# Volumetric_Control_Board.net
KiCad netlist of a schematic drawn in EAGLE
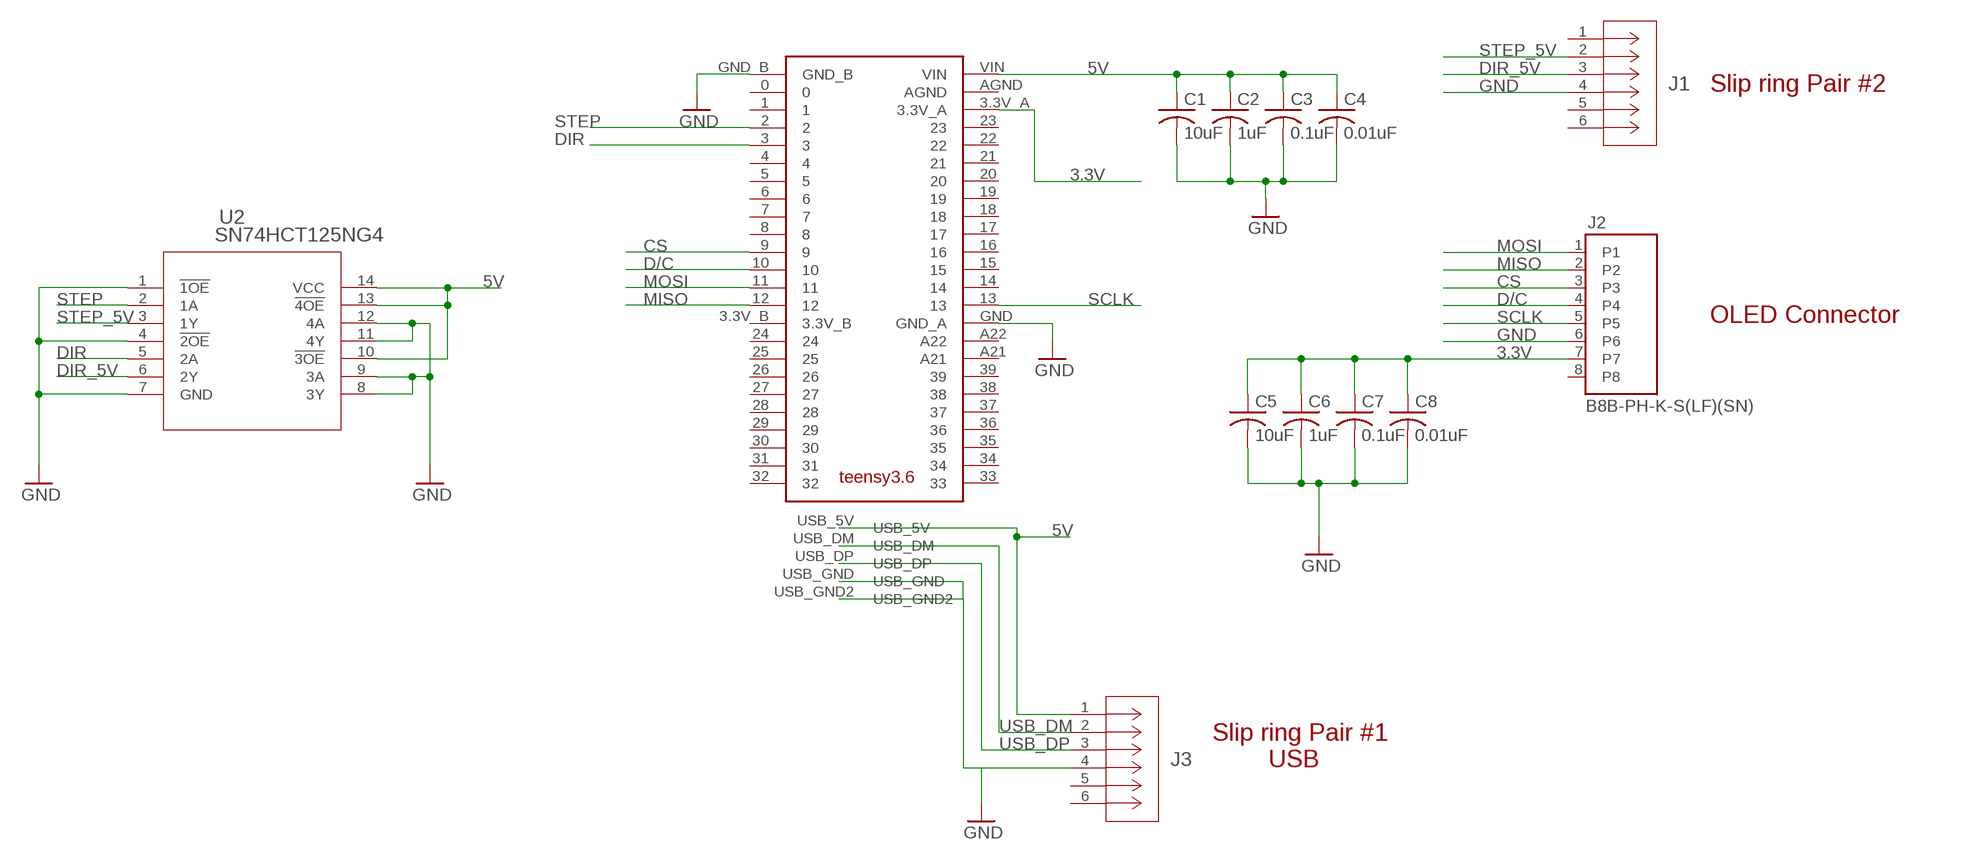
[diagram p0: schematic, sheet 1]

(export (version "E")
  (design (tool "Eeschema 10.0.6"))
  (components
    (comp (ref "C1")
      (value "10uF")
      (footprint "eagle-import:C1206")
      (libsource (lib "eagle-import") (part "C-USC1206"))
    )
    (comp (ref "C2")
      (value "1uF")
      (footprint "eagle-import:C1206")
      (libsource (lib "eagle-import") (part "C-USC1206"))
    )
    (comp (ref "C3")
      (value "0.1uF")
      (footprint "eagle-import:C1206")
      (libsource (lib "eagle-import") (part "C-USC1206"))
    )
    (comp (ref "C4")
      (value "0.01uF")
      (footprint "eagle-import:C1206")
      (libsource (lib "eagle-import") (part "C-USC1206"))
    )
    (comp (ref "C5")
      (value "10uF")
      (footprint "eagle-import:C1206")
      (libsource (lib "eagle-import") (part "C-USC1206"))
    )
    (comp (ref "C6")
      (value "1uF")
      (footprint "eagle-import:C1206")
      (libsource (lib "eagle-import") (part "C-USC1206"))
    )
    (comp (ref "C7")
      (value "0.1uF")
      (footprint "eagle-import:C1206")
      (libsource (lib "eagle-import") (part "C-USC1206"))
    )
    (comp (ref "C8")
      (value "0.01uF")
      (footprint "eagle-import:C1206")
      (libsource (lib "eagle-import") (part "C-USC1206"))
    )
    (comp (ref "J1")
      (value "B6B-PH-K-S(LF)(SN)")
      (footprint "eagle-import:CONN_B6B-PH-K-S_JST")
      (fields (field (name "COPYRIGHT") "Copyright (C) 2021 Ultra Librarian. All rights reserved."))
      (libsource (lib "eagle-import") (part "B6B-PH-K-S(LF)(SN)"))
    )
    (comp (ref "J2")
      (value "B8B-PH-K-S(LF)(SN)")
      (footprint "eagle-import:JST_B8B-PH-K-S(LF)(SN)")
      (fields (field (name "DIGI-KEY_PART_NUMBER") "455-1710-ND") (field (name "MF") "JST Sales"))
      (libsource (lib "eagle-import") (part "B8B-PH-K-S(LF)(SN)"))
    )
    (comp (ref "J3")
      (value "B6B-PH-K-S(LF)(SN)")
      (footprint "eagle-import:CONN_B6B-PH-K-S_JST")
      (fields (field (name "COPYRIGHT") "Copyright (C) 2021 Ultra Librarian. All rights reserved."))
      (libsource (lib "eagle-import") (part "B6B-PH-K-S(LF)(SN)"))
    )
    (comp (ref "U$1")
      (value "TEENSY3.6")
      (footprint "eagle-import:TEENSY3.6")
      (libsource (lib "eagle-import") (part "TEENSY3.6"))
    )
    (comp (ref "U2")
      (value "SN74HCT125NG4")
      (footprint "eagle-import:N14_TEX")
      (fields (field (name "COPYRIGHT") "Copyright (C) 2021 Ultra Librarian. All rights reserved."))
      (libsource (lib "eagle-import") (part "SN74HCT125NG4"))
    )
  )
  (nets
    (net (code "1") (name "/3.3V") (class "Default")
      (node (ref "C5") (pin "1") (pinfunction "1_1") (pintype "passive"))
      (node (ref "C6") (pin "1") (pinfunction "1_1") (pintype "passive"))
      (node (ref "C7") (pin "1") (pinfunction "1_1") (pintype "passive"))
      (node (ref "C8") (pin "1") (pinfunction "1_1") (pintype "passive"))
      (node (ref "J2") (pin "7") (pinfunction "P7_7") (pintype "passive"))
      (node (ref "U$1") (pin "3.3V_A") (pinfunction "3.3V_A_3.3V_A") (pintype "bidirectional"))
    )
    (net (code "2") (name "/5V") (class "Default")
      (node (ref "C1") (pin "1") (pinfunction "1_1") (pintype "passive"))
      (node (ref "C2") (pin "1") (pinfunction "1_1") (pintype "passive"))
      (node (ref "C3") (pin "1") (pinfunction "1_1") (pintype "passive"))
      (node (ref "C4") (pin "1") (pinfunction "1_1") (pintype "passive"))
      (node (ref "J3") (pin "1") (pinfunction "1_1") (pintype "passive"))
      (node (ref "U$1") (pin "USB_5V") (pinfunction "USB_5V_USB_5V") (pintype "bidirectional"))
      (node (ref "U$1") (pin "VIN") (pinfunction "VIN_VIN") (pintype "bidirectional"))
      (node (ref "U2") (pin "10") (pinfunction "~{3OE}_10") (pintype "input"))
      (node (ref "U2") (pin "13") (pinfunction "~{4OE}_13") (pintype "input"))
      (node (ref "U2") (pin "14") (pinfunction "VCC_14") (pintype "passive"))
    )
    (net (code "3") (name "/CS") (class "Default")
      (node (ref "J2") (pin "3") (pinfunction "P3_3") (pintype "passive"))
      (node (ref "U$1") (pin "9") (pinfunction "9_9") (pintype "bidirectional"))
    )
    (net (code "4") (name "/DIR") (class "Default")
      (node (ref "U$1") (pin "3") (pinfunction "3_3") (pintype "bidirectional"))
      (node (ref "U2") (pin "5") (pinfunction "2A_5") (pintype "input"))
    )
    (net (code "5") (name "/DIR_5V") (class "Default")
      (node (ref "J1") (pin "3") (pinfunction "3_3") (pintype "passive"))
      (node (ref "U2") (pin "6") (pinfunction "2Y_6") (pintype "tri_state"))
    )
    (net (code "6") (name "/D{slash}C") (class "Default")
      (node (ref "J2") (pin "4") (pinfunction "P4_4") (pintype "passive"))
      (node (ref "U$1") (pin "10") (pinfunction "10_10") (pintype "bidirectional"))
    )
    (net (code "7") (name "/MISO") (class "Default")
      (node (ref "J2") (pin "2") (pinfunction "P2_2") (pintype "passive"))
      (node (ref "U$1") (pin "12") (pinfunction "12_12") (pintype "bidirectional"))
    )
    (net (code "8") (name "/MOSI") (class "Default")
      (node (ref "J2") (pin "1") (pinfunction "P1_1") (pintype "passive"))
      (node (ref "U$1") (pin "11") (pinfunction "11_11") (pintype "bidirectional"))
    )
    (net (code "9") (name "/SCLK") (class "Default")
      (node (ref "J2") (pin "5") (pinfunction "P5_5") (pintype "passive"))
      (node (ref "U$1") (pin "13") (pinfunction "13_13") (pintype "bidirectional"))
    )
    (net (code "10") (name "/STEP") (class "Default")
      (node (ref "U$1") (pin "2") (pinfunction "2_2") (pintype "bidirectional"))
      (node (ref "U2") (pin "2") (pinfunction "1A_2") (pintype "input"))
    )
    (net (code "11") (name "/STEP_5V") (class "Default")
      (node (ref "J1") (pin "2") (pinfunction "2_2") (pintype "passive"))
      (node (ref "U2") (pin "3") (pinfunction "1Y_3") (pintype "tri_state"))
    )
    (net (code "12") (name "/USB_DM") (class "Default")
      (node (ref "J3") (pin "2") (pinfunction "2_2") (pintype "passive"))
      (node (ref "U$1") (pin "USB_DM") (pinfunction "USB_DM_USB_DM") (pintype "bidirectional"))
    )
    (net (code "13") (name "/USB_DP") (class "Default")
      (node (ref "J3") (pin "3") (pinfunction "3_3") (pintype "passive"))
      (node (ref "U$1") (pin "USB_DP") (pinfunction "USB_DP_USB_DP") (pintype "bidirectional"))
    )
    (net (code "14") (name "GND") (class "Default")
      (node (ref "C1") (pin "2") (pinfunction "2_2") (pintype "passive"))
      (node (ref "C2") (pin "2") (pinfunction "2_2") (pintype "passive"))
      (node (ref "C3") (pin "2") (pinfunction "2_2") (pintype "passive"))
      (node (ref "C4") (pin "2") (pinfunction "2_2") (pintype "passive"))
      (node (ref "C5") (pin "2") (pinfunction "2_2") (pintype "passive"))
      (node (ref "C6") (pin "2") (pinfunction "2_2") (pintype "passive"))
      (node (ref "C7") (pin "2") (pinfunction "2_2") (pintype "passive"))
      (node (ref "C8") (pin "2") (pinfunction "2_2") (pintype "passive"))
      (node (ref "J1") (pin "4") (pinfunction "4_4") (pintype "passive"))
      (node (ref "J2") (pin "6") (pinfunction "P6_6") (pintype "passive"))
      (node (ref "J3") (pin "4") (pinfunction "4_4") (pintype "passive"))
      (node (ref "U$1") (pin "GND") (pinfunction "GND_A_GND") (pintype "bidirectional"))
      (node (ref "U$1") (pin "GND_B") (pinfunction "GND_B_GND_B") (pintype "bidirectional"))
      (node (ref "U$1") (pin "USB_GND") (pinfunction "USB_GND_USB_GND") (pintype "bidirectional"))
      (node (ref "U$1") (pin "USB_GND2") (pinfunction "USB_GND2_USB_GND2") (pintype "bidirectional"))
      (node (ref "U2") (pin "1") (pinfunction "~{1OE}_1") (pintype "input"))
      (node (ref "U2") (pin "11") (pinfunction "4Y_11") (pintype "tri_state"))
      (node (ref "U2") (pin "12") (pinfunction "4A_12") (pintype "input"))
      (node (ref "U2") (pin "4") (pinfunction "~{2OE}_4") (pintype "input"))
      (node (ref "U2") (pin "7") (pinfunction "GND_7") (pintype "passive"))
      (node (ref "U2") (pin "8") (pinfunction "3Y_8") (pintype "tri_state"))
      (node (ref "U2") (pin "9") (pinfunction "3A_9") (pintype "input"))
    )
    (net (code "15") (name "unconnected-(J1-Pad1)") (class "Default")
      (node (ref "J1") (pin "1") (pinfunction "1_1") (pintype "passive"))
    )
    (net (code "16") (name "unconnected-(J1-Pad5)") (class "Default")
      (node (ref "J1") (pin "5") (pinfunction "5_5") (pintype "passive"))
    )
    (net (code "17") (name "unconnected-(J1-Pad6)") (class "Default")
      (node (ref "J1") (pin "6") (pinfunction "6_6") (pintype "passive"))
    )
    (net (code "18") (name "unconnected-(J2-P8-Pad8)") (class "Default")
      (node (ref "J2") (pin "8") (pinfunction "P8_8") (pintype "passive"))
    )
    (net (code "19") (name "unconnected-(J3-Pad5)") (class "Default")
      (node (ref "J3") (pin "5") (pinfunction "5_5") (pintype "passive"))
    )
    (net (code "20") (name "unconnected-(J3-Pad6)") (class "Default")
      (node (ref "J3") (pin "6") (pinfunction "6_6") (pintype "passive"))
    )
    (net (code "21") (name "unconnected-(U$1-Pad0)") (class "Default")
      (node (ref "U$1") (pin "0") (pinfunction "0_0") (pintype "bidirectional"))
    )
    (net (code "22") (name "unconnected-(U$1-Pad1)") (class "Default")
      (node (ref "U$1") (pin "1") (pinfunction "1_1") (pintype "bidirectional"))
    )
    (net (code "23") (name "unconnected-(U$1-Pad3.3V_B)") (class "Default")
      (node (ref "U$1") (pin "3.3V_B") (pinfunction "3.3V_B_3.3V_B") (pintype "bidirectional"))
    )
    (net (code "24") (name "unconnected-(U$1-Pad4)") (class "Default")
      (node (ref "U$1") (pin "4") (pinfunction "4_4") (pintype "bidirectional"))
    )
    (net (code "25") (name "unconnected-(U$1-Pad5)") (class "Default")
      (node (ref "U$1") (pin "5") (pinfunction "5_5") (pintype "bidirectional"))
    )
    (net (code "26") (name "unconnected-(U$1-Pad6)") (class "Default")
      (node (ref "U$1") (pin "6") (pinfunction "6_6") (pintype "bidirectional"))
    )
    (net (code "27") (name "unconnected-(U$1-Pad7)") (class "Default")
      (node (ref "U$1") (pin "7") (pinfunction "7_7") (pintype "bidirectional"))
    )
    (net (code "28") (name "unconnected-(U$1-Pad8)") (class "Default")
      (node (ref "U$1") (pin "8") (pinfunction "8_8") (pintype "bidirectional"))
    )
    (net (code "29") (name "unconnected-(U$1-Pad14)") (class "Default")
      (node (ref "U$1") (pin "14") (pinfunction "14_14") (pintype "bidirectional"))
    )
    (net (code "30") (name "unconnected-(U$1-Pad15)") (class "Default")
      (node (ref "U$1") (pin "15") (pinfunction "15_15") (pintype "bidirectional"))
    )
    (net (code "31") (name "unconnected-(U$1-Pad16)") (class "Default")
      (node (ref "U$1") (pin "16") (pinfunction "16_16") (pintype "bidirectional"))
    )
    (net (code "32") (name "unconnected-(U$1-Pad17)") (class "Default")
      (node (ref "U$1") (pin "17") (pinfunction "17_17") (pintype "bidirectional"))
    )
    (net (code "33") (name "unconnected-(U$1-Pad18)") (class "Default")
      (node (ref "U$1") (pin "18") (pinfunction "18_18") (pintype "bidirectional"))
    )
    (net (code "34") (name "unconnected-(U$1-Pad19)") (class "Default")
      (node (ref "U$1") (pin "19") (pinfunction "19_19") (pintype "bidirectional"))
    )
    (net (code "35") (name "unconnected-(U$1-Pad20)") (class "Default")
      (node (ref "U$1") (pin "20") (pinfunction "20_20") (pintype "bidirectional"))
    )
    (net (code "36") (name "unconnected-(U$1-Pad21)") (class "Default")
      (node (ref "U$1") (pin "21") (pinfunction "21_21") (pintype "bidirectional"))
    )
    (net (code "37") (name "unconnected-(U$1-Pad22)") (class "Default")
      (node (ref "U$1") (pin "22") (pinfunction "22_22") (pintype "bidirectional"))
    )
    (net (code "38") (name "unconnected-(U$1-Pad23)") (class "Default")
      (node (ref "U$1") (pin "23") (pinfunction "23_23") (pintype "bidirectional"))
    )
    (net (code "39") (name "unconnected-(U$1-Pad24)") (class "Default")
      (node (ref "U$1") (pin "24") (pinfunction "24_24") (pintype "bidirectional"))
    )
    (net (code "40") (name "unconnected-(U$1-Pad25)") (class "Default")
      (node (ref "U$1") (pin "25") (pinfunction "25_25") (pintype "bidirectional"))
    )
    (net (code "41") (name "unconnected-(U$1-Pad26)") (class "Default")
      (node (ref "U$1") (pin "26") (pinfunction "26_26") (pintype "bidirectional"))
    )
    (net (code "42") (name "unconnected-(U$1-Pad27)") (class "Default")
      (node (ref "U$1") (pin "27") (pinfunction "27_27") (pintype "bidirectional"))
    )
    (net (code "43") (name "unconnected-(U$1-Pad28)") (class "Default")
      (node (ref "U$1") (pin "28") (pinfunction "28_28") (pintype "bidirectional"))
    )
    (net (code "44") (name "unconnected-(U$1-Pad29)") (class "Default")
      (node (ref "U$1") (pin "29") (pinfunction "29_29") (pintype "bidirectional"))
    )
    (net (code "45") (name "unconnected-(U$1-Pad30)") (class "Default")
      (node (ref "U$1") (pin "30") (pinfunction "30_30") (pintype "bidirectional"))
    )
    (net (code "46") (name "unconnected-(U$1-Pad31)") (class "Default")
      (node (ref "U$1") (pin "31") (pinfunction "31_31") (pintype "bidirectional"))
    )
    (net (code "47") (name "unconnected-(U$1-Pad32)") (class "Default")
      (node (ref "U$1") (pin "32") (pinfunction "32_32") (pintype "bidirectional"))
    )
    (net (code "48") (name "unconnected-(U$1-Pad33)") (class "Default")
      (node (ref "U$1") (pin "33") (pinfunction "33_33") (pintype "bidirectional"))
    )
    (net (code "49") (name "unconnected-(U$1-Pad34)") (class "Default")
      (node (ref "U$1") (pin "34") (pinfunction "34_34") (pintype "bidirectional"))
    )
    (net (code "50") (name "unconnected-(U$1-Pad35)") (class "Default")
      (node (ref "U$1") (pin "35") (pinfunction "35_35") (pintype "bidirectional"))
    )
    (net (code "51") (name "unconnected-(U$1-Pad36)") (class "Default")
      (node (ref "U$1") (pin "36") (pinfunction "36_36") (pintype "bidirectional"))
    )
    (net (code "52") (name "unconnected-(U$1-Pad37)") (class "Default")
      (node (ref "U$1") (pin "37") (pinfunction "37_37") (pintype "bidirectional"))
    )
    (net (code "53") (name "unconnected-(U$1-Pad38)") (class "Default")
      (node (ref "U$1") (pin "38") (pinfunction "38_38") (pintype "bidirectional"))
    )
    (net (code "54") (name "unconnected-(U$1-Pad39)") (class "Default")
      (node (ref "U$1") (pin "39") (pinfunction "39_39") (pintype "bidirectional"))
    )
    (net (code "55") (name "unconnected-(U$1-PadA21)") (class "Default")
      (node (ref "U$1") (pin "A21") (pinfunction "A21_A21") (pintype "bidirectional"))
    )
    (net (code "56") (name "unconnected-(U$1-PadA22)") (class "Default")
      (node (ref "U$1") (pin "A22") (pinfunction "A22_A22") (pintype "bidirectional"))
    )
    (net (code "57") (name "unconnected-(U$1-PadAGND)") (class "Default")
      (node (ref "U$1") (pin "AGND") (pinfunction "AGND_AGND") (pintype "bidirectional"))
    )
  )
)
